# adxl357.net
KiCad netlist of a schematic drawn in Altium Designer
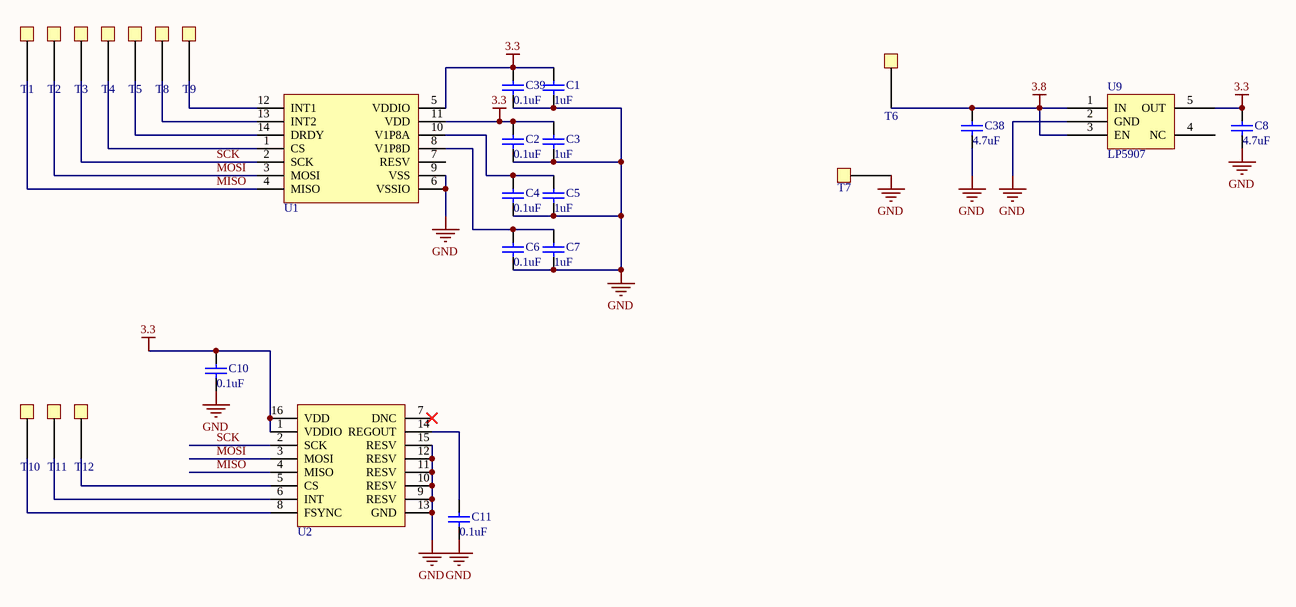
[diagram p0: adxl357.SchDoc]

(export (version "E")
  (design (tool "Eeschema 10.0.6"))
  (components
    (comp (ref "C1")
      (value "1uF")
      (footprint "0402")
      (description "Capacitor")
      (fields (field (name "PUBLISHER") "Altium Limited"))
      (libsource (lib "RTC6705") (part "Cap"))
    )
    (comp (ref "C2")
      (value "0.1uF")
      (footprint "0402")
      (description "Capacitor")
      (fields (field (name "PUBLISHER") "Altium Limited"))
      (libsource (lib "RTC6705") (part "Cap"))
    )
    (comp (ref "C3")
      (value "1uF")
      (footprint "0402")
      (description "Capacitor")
      (fields (field (name "PUBLISHER") "Altium Limited"))
      (libsource (lib "RTC6705") (part "Cap"))
    )
    (comp (ref "C4")
      (value "0.1uF")
      (footprint "0402")
      (description "Capacitor")
      (fields (field (name "PUBLISHER") "Altium Limited"))
      (libsource (lib "RTC6705") (part "Cap"))
    )
    (comp (ref "C5")
      (value "1uF")
      (footprint "0402")
      (description "Capacitor")
      (fields (field (name "PUBLISHER") "Altium Limited"))
      (libsource (lib "RTC6705") (part "Cap"))
    )
    (comp (ref "C6")
      (value "0.1uF")
      (footprint "0402")
      (description "Capacitor")
      (fields (field (name "PUBLISHER") "Altium Limited"))
      (libsource (lib "RTC6705") (part "Cap"))
    )
    (comp (ref "C7")
      (value "1uF")
      (footprint "0402")
      (description "Capacitor")
      (fields (field (name "PUBLISHER") "Altium Limited"))
      (libsource (lib "RTC6705") (part "Cap"))
    )
    (comp (ref "C8")
      (value "4.7uF")
      (footprint "0603L")
      (description "Capacitor")
      (fields (field (name "PUBLISHER") "Altium Limited"))
      (libsource (lib "RTC6705") (part "Cap"))
    )
    (comp (ref "C10")
      (value "0.1uF")
      (footprint "0402")
      (description "Capacitor")
      (fields (field (name "PUBLISHER") "Altium Limited"))
      (libsource (lib "RTC6705") (part "Cap"))
    )
    (comp (ref "C11")
      (value "0.1uF")
      (footprint "0402")
      (description "Capacitor")
      (fields (field (name "PUBLISHER") "Altium Limited"))
      (libsource (lib "RTC6705") (part "Cap"))
    )
    (comp (ref "C38")
      (value "4.7uF")
      (footprint "0603L")
      (description "Capacitor")
      (fields (field (name "PUBLISHER") "Altium Limited"))
      (libsource (lib "RTC6705") (part "Cap"))
    )
    (comp (ref "C39")
      (value "0.1uF")
      (footprint "0402")
      (description "Capacitor")
      (fields (field (name "PUBLISHER") "Altium Limited"))
      (libsource (lib "RTC6705") (part "Cap"))
    )
    (comp (ref "T1") (value "TestPad") (footprint "TestPad - 1mm") (libsource (lib "sch") (part "TestPad")))
    (comp (ref "T2") (value "TestPad") (footprint "TestPad - 1mm") (libsource (lib "sch") (part "TestPad")))
    (comp (ref "T3") (value "TestPad") (footprint "TestPad - 1mm") (libsource (lib "sch") (part "TestPad")))
    (comp (ref "T4") (value "TestPad") (footprint "TestPad - 1mm") (libsource (lib "sch") (part "TestPad")))
    (comp (ref "T5") (value "TestPad") (footprint "TestPad - 1mm") (libsource (lib "sch") (part "TestPad")))
    (comp (ref "T6") (value "TestPad") (footprint "TestPad - 1mm") (libsource (lib "sch") (part "TestPad")))
    (comp (ref "T7") (value "TestPad") (footprint "TestPad - 1mm") (libsource (lib "") (part "TestPad_1")))
    (comp (ref "T8") (value "TestPad") (footprint "TestPad - 1mm") (libsource (lib "sch") (part "TestPad")))
    (comp (ref "T9") (value "TestPad") (footprint "TestPad - 1mm") (libsource (lib "sch") (part "TestPad")))
    (comp (ref "T10") (value "TestPad") (footprint "TestPad - 1mm") (libsource (lib "sch") (part "TestPad")))
    (comp (ref "T11") (value "TestPad") (footprint "TestPad - 1mm") (libsource (lib "sch") (part "TestPad")))
    (comp (ref "T12") (value "TestPad") (footprint "TestPad - 1mm") (libsource (lib "sch") (part "TestPad")))
    (comp (ref "U1") (value "ADXL357") (footprint "ADXL357") (libsource (lib "ADXL357") (part "ADXL357")))
    (comp (ref "U2") (value "ICM20602") (footprint "ICM20602") (libsource (lib "ADXL357") (part "ICM20602")))
    (comp (ref "U9") (value "LP5907") (footprint "SOT23-5") (libsource (lib "RTC6705") (part "LP5907")))
  )
  (nets
    (net (code "1") (name "/MISO") (class "Default")
      (node (ref "T1") (pin "1") (pinfunction "3_1") (pintype "passive"))
      (node (ref "U1") (pin "4") (pinfunction "MISO_4") (pintype "passive"))
      (node (ref "U2") (pin "4") (pinfunction "MISO_4") (pintype "passive"))
    )
    (net (code "2") (name "/MOSI") (class "Default")
      (node (ref "T2") (pin "1") (pinfunction "3_1") (pintype "passive"))
      (node (ref "U1") (pin "3") (pinfunction "MOSI_3") (pintype "passive"))
      (node (ref "U2") (pin "3") (pinfunction "MOSI_3") (pintype "passive"))
    )
    (net (code "3") (name "/SCK") (class "Default")
      (node (ref "T3") (pin "1") (pinfunction "3_1") (pintype "passive"))
      (node (ref "U1") (pin "2") (pinfunction "SCK_2") (pintype "passive"))
      (node (ref "U2") (pin "2") (pinfunction "SCK_2") (pintype "passive"))
    )
    (net (code "4") (name "3.3") (class "Default")
      (node (ref "C1") (pin "2") (pinfunction "2_2") (pintype "passive"))
      (node (ref "C10") (pin "2") (pinfunction "2_2") (pintype "passive"))
      (node (ref "C2") (pin "2") (pinfunction "2_2") (pintype "passive"))
      (node (ref "C3") (pin "2") (pinfunction "2_2") (pintype "passive"))
      (node (ref "C39") (pin "2") (pinfunction "2_2") (pintype "passive"))
      (node (ref "C8") (pin "2") (pinfunction "2_2") (pintype "passive"))
      (node (ref "U1") (pin "11") (pinfunction "VDD_11") (pintype "passive"))
      (node (ref "U1") (pin "5") (pinfunction "VDDIO_5") (pintype "passive"))
      (node (ref "U2") (pin "1") (pinfunction "VDDIO_1") (pintype "passive"))
      (node (ref "U2") (pin "16") (pinfunction "VDD_16") (pintype "passive"))
      (node (ref "U9") (pin "5") (pinfunction "OUT_5") (pintype "passive"))
    )
    (net (code "5") (name "3.8") (class "Default")
      (node (ref "C38") (pin "2") (pinfunction "2_2") (pintype "passive"))
      (node (ref "T6") (pin "1") (pinfunction "3_1") (pintype "passive"))
      (node (ref "U9") (pin "1") (pinfunction "IN_1") (pintype "passive"))
      (node (ref "U9") (pin "3") (pinfunction "EN_3") (pintype "passive"))
    )
    (net (code "6") (name "GND") (class "Default")
      (node (ref "C1") (pin "1") (pinfunction "1_1") (pintype "passive"))
      (node (ref "C10") (pin "1") (pinfunction "1_1") (pintype "passive"))
      (node (ref "C11") (pin "1") (pinfunction "1_1") (pintype "passive"))
      (node (ref "C2") (pin "1") (pinfunction "1_1") (pintype "passive"))
      (node (ref "C3") (pin "1") (pinfunction "1_1") (pintype "passive"))
      (node (ref "C38") (pin "1") (pinfunction "1_1") (pintype "passive"))
      (node (ref "C39") (pin "1") (pinfunction "1_1") (pintype "passive"))
      (node (ref "C4") (pin "1") (pinfunction "1_1") (pintype "passive"))
      (node (ref "C5") (pin "1") (pinfunction "1_1") (pintype "passive"))
      (node (ref "C6") (pin "1") (pinfunction "1_1") (pintype "passive"))
      (node (ref "C7") (pin "1") (pinfunction "1_1") (pintype "passive"))
      (node (ref "C8") (pin "1") (pinfunction "1_1") (pintype "passive"))
      (node (ref "T7") (pin "1") (pinfunction "3_1") (pintype "passive"))
      (node (ref "U1") (pin "6") (pinfunction "VSSIO_6") (pintype "passive"))
      (node (ref "U1") (pin "9") (pinfunction "VSS_9") (pintype "passive"))
      (node (ref "U2") (pin "10") (pinfunction "RESV_10") (pintype "passive"))
      (node (ref "U2") (pin "11") (pinfunction "RESV_11") (pintype "passive"))
      (node (ref "U2") (pin "12") (pinfunction "RESV_12") (pintype "passive"))
      (node (ref "U2") (pin "13") (pinfunction "GND_13") (pintype "passive"))
      (node (ref "U2") (pin "15") (pinfunction "RESV_15") (pintype "passive"))
      (node (ref "U2") (pin "9") (pinfunction "RESV_9") (pintype "passive"))
      (node (ref "U9") (pin "2") (pinfunction "GND_2") (pintype "passive"))
    )
    (net (code "7") (name "Net-(T4-3)") (class "Default")
      (node (ref "T4") (pin "1") (pinfunction "3_1") (pintype "passive"))
      (node (ref "U1") (pin "1") (pinfunction "CS_1") (pintype "passive"))
    )
    (net (code "8") (name "Net-(T5-3)") (class "Default")
      (node (ref "T5") (pin "1") (pinfunction "3_1") (pintype "passive"))
      (node (ref "U1") (pin "14") (pinfunction "DRDY_14") (pintype "passive"))
    )
    (net (code "9") (name "Net-(T8-3)") (class "Default")
      (node (ref "T8") (pin "1") (pinfunction "3_1") (pintype "passive"))
      (node (ref "U1") (pin "13") (pinfunction "INT2_13") (pintype "passive"))
    )
    (net (code "10") (name "Net-(T9-3)") (class "Default")
      (node (ref "T9") (pin "1") (pinfunction "3_1") (pintype "passive"))
      (node (ref "U1") (pin "12") (pinfunction "INT1_12") (pintype "passive"))
    )
    (net (code "11") (name "Net-(T10-3)") (class "Default")
      (node (ref "T10") (pin "1") (pinfunction "3_1") (pintype "passive"))
      (node (ref "U2") (pin "8") (pinfunction "FSYNC_8") (pintype "passive"))
    )
    (net (code "12") (name "Net-(T11-3)") (class "Default")
      (node (ref "T11") (pin "1") (pinfunction "3_1") (pintype "passive"))
      (node (ref "U2") (pin "6") (pinfunction "INT_6") (pintype "passive"))
    )
    (net (code "13") (name "Net-(T12-3)") (class "Default")
      (node (ref "T12") (pin "1") (pinfunction "3_1") (pintype "passive"))
      (node (ref "U2") (pin "5") (pinfunction "CS_5") (pintype "passive"))
    )
    (net (code "14") (name "Net-(U1-V1P8A)") (class "Default")
      (node (ref "C4") (pin "2") (pinfunction "2_2") (pintype "passive"))
      (node (ref "C5") (pin "2") (pinfunction "2_2") (pintype "passive"))
      (node (ref "U1") (pin "10") (pinfunction "V1P8A_10") (pintype "passive"))
    )
    (net (code "15") (name "Net-(U1-V1P8D)") (class "Default")
      (node (ref "C6") (pin "2") (pinfunction "2_2") (pintype "passive"))
      (node (ref "C7") (pin "2") (pinfunction "2_2") (pintype "passive"))
      (node (ref "U1") (pin "8") (pinfunction "V1P8D_8") (pintype "passive"))
    )
    (net (code "16") (name "Net-(U2-REGOUT)") (class "Default")
      (node (ref "C11") (pin "2") (pinfunction "2_2") (pintype "passive"))
      (node (ref "U2") (pin "14") (pinfunction "REGOUT_14") (pintype "passive"))
    )
    (net (code "17") (name "unconnected-(U1-RESV-Pad7)") (class "Default")
      (node (ref "U1") (pin "7") (pinfunction "RESV_7") (pintype "passive"))
    )
    (net (code "18") (name "unconnected-(U2-DNC-Pad7)") (class "Default")
      (node (ref "U2") (pin "7") (pinfunction "DNC_7") (pintype "passive+no_connect"))
    )
    (net (code "19") (name "unconnected-(U9-NC-Pad4)") (class "Default")
      (node (ref "U9") (pin "4") (pinfunction "NC_4") (pintype "passive"))
    )
  )
)
